# PixiFlood_PTH.net
KiCad netlist of a schematic drawn in EAGLE
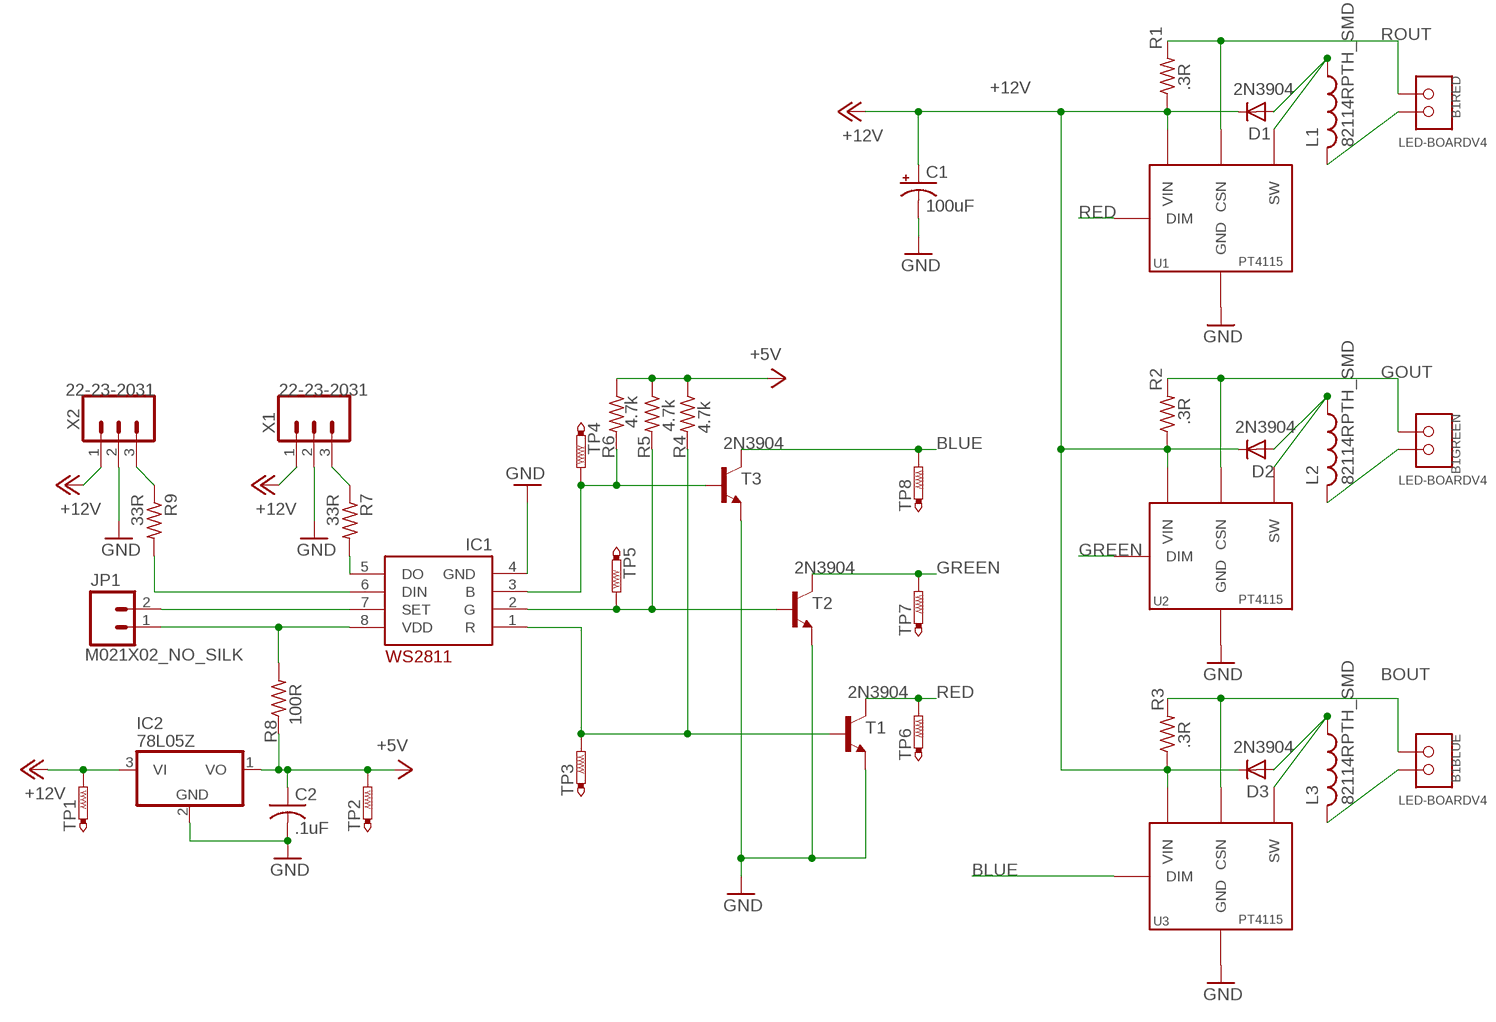
[diagram p0: schematic, sheet 1]

(export (version "E")
  (design (tool "Eeschema 10.0.6"))
  (components
    (comp (ref "B1")
      (value "LED-BOARDV4")
      (footprint "eagle-import:LED_BOARD-V4")
      (libsource (lib "eagle-import") (part "LED-BOARDV4"))
    )
    (comp (ref "C1")
      (value "100uF")
      (footprint "eagle-import:TT2D6L")
      (libsource (lib "eagle-import") (part "CPOL-USTT2D6L"))
    )
    (comp (ref "C2")
      (value ".1uF")
      (footprint "eagle-import:C050-024X044")
      (libsource (lib "eagle-import") (part "C-US050-024X044"))
    )
    (comp (ref "D1")
      (value "2N3904")
      (footprint "eagle-import:DO07")
      (libsource (lib "eagle-import") (part "DIODE-DO07"))
    )
    (comp (ref "D2")
      (value "2N3904")
      (footprint "eagle-import:DO07")
      (libsource (lib "eagle-import") (part "DIODE-DO07"))
    )
    (comp (ref "D3")
      (value "2N3904")
      (footprint "eagle-import:DO07")
      (libsource (lib "eagle-import") (part "DIODE-DO07"))
    )
    (comp (ref "IC1")
      (value "WS2811-SOP8")
      (footprint "eagle-import:SO08-SKINNYPADS")
      (libsource (lib "eagle-import") (part "WS2811-SOP8"))
    )
    (comp (ref "IC2")
      (value "78L05Z")
      (footprint "eagle-import:TO92")
      (libsource (lib "eagle-import") (part "78ZL05"))
    )
    (comp (ref "JP1")
      (value "M021X02_NO_SILK")
      (footprint "eagle-import:1X02_NO_SILK")
      (libsource (lib "eagle-import") (part "M021X02_NO_SILK"))
    )
    (comp (ref "L1")
      (value "82114RPTH_SMD")
      (footprint "eagle-import:INDUCTOR")
      (libsource (lib "eagle-import") (part "82114RPTH_SMD"))
    )
    (comp (ref "L2")
      (value "82114RPTH_SMD")
      (footprint "eagle-import:INDUCTOR")
      (libsource (lib "eagle-import") (part "82114RPTH_SMD"))
    )
    (comp (ref "L3")
      (value "82114RPTH_SMD")
      (footprint "eagle-import:INDUCTOR")
      (libsource (lib "eagle-import") (part "82114RPTH_SMD"))
    )
    (comp (ref "R1")
      (value ".3R")
      (footprint "eagle-import:0204_7")
      (libsource (lib "eagle-import") (part "resistor_R-US_0204/7"))
    )
    (comp (ref "R2")
      (value ".3R")
      (footprint "eagle-import:0204_7")
      (libsource (lib "eagle-import") (part "resistor_R-US_0204/7"))
    )
    (comp (ref "R3")
      (value ".3R")
      (footprint "eagle-import:0204_7")
      (libsource (lib "eagle-import") (part "resistor_R-US_0204/7"))
    )
    (comp (ref "R4")
      (value "4.7k")
      (footprint "eagle-import:0204_7")
      (libsource (lib "eagle-import") (part "resistor_R-US_0204/7"))
    )
    (comp (ref "R5")
      (value "4.7k")
      (footprint "eagle-import:0204_7")
      (libsource (lib "eagle-import") (part "resistor_R-US_0204/7"))
    )
    (comp (ref "R6")
      (value "4.7k")
      (footprint "eagle-import:0204_7")
      (libsource (lib "eagle-import") (part "resistor_R-US_0204/7"))
    )
    (comp (ref "R7")
      (value "33R")
      (footprint "eagle-import:0204_7")
      (libsource (lib "eagle-import") (part "R-US_0204/7"))
    )
    (comp (ref "R8")
      (value "100R")
      (footprint "eagle-import:0204_7")
      (libsource (lib "eagle-import") (part "R-US_0204/7"))
    )
    (comp (ref "R9")
      (value "33R")
      (footprint "eagle-import:0204_7")
      (libsource (lib "eagle-import") (part "R-US_0204/7"))
    )
    (comp (ref "T1")
      (value "2N3904")
      (footprint "eagle-import:TO92")
      (libsource (lib "eagle-import") (part "2N3904"))
    )
    (comp (ref "T2")
      (value "2N3904")
      (footprint "eagle-import:TO92")
      (libsource (lib "eagle-import") (part "2N3904"))
    )
    (comp (ref "T3")
      (value "2N3904")
      (footprint "eagle-import:TO92")
      (libsource (lib "eagle-import") (part "2N3904"))
    )
    (comp (ref "TP1")
      (value "PTR1B2,54")
      (footprint "eagle-import:B2,54")
      (libsource (lib "eagle-import") (part "PTR1B2,54"))
    )
    (comp (ref "TP2")
      (value "PTR1B2,54")
      (footprint "eagle-import:B2,54")
      (libsource (lib "eagle-import") (part "PTR1B2,54"))
    )
    (comp (ref "TP3")
      (value "PTR1B1,27")
      (footprint "eagle-import:B1,27")
      (libsource (lib "eagle-import") (part "PTR1B1,27"))
    )
    (comp (ref "TP4")
      (value "PTR1B1,27")
      (footprint "eagle-import:B1,27")
      (libsource (lib "eagle-import") (part "PTR1B1,27"))
    )
    (comp (ref "TP5")
      (value "PTR1B1,27")
      (footprint "eagle-import:B1,27")
      (libsource (lib "eagle-import") (part "PTR1B1,27"))
    )
    (comp (ref "TP6")
      (value "PTR1B1,27")
      (footprint "eagle-import:B1,27")
      (libsource (lib "eagle-import") (part "PTR1B1,27"))
    )
    (comp (ref "TP7")
      (value "PTR1B1,27")
      (footprint "eagle-import:B1,27")
      (libsource (lib "eagle-import") (part "PTR1B1,27"))
    )
    (comp (ref "TP8")
      (value "PTR1B1,27")
      (footprint "eagle-import:B1,27")
      (libsource (lib "eagle-import") (part "PTR1B1,27"))
    )
    (comp (ref "U1")
      (value "PT4115B89E")
      (footprint "eagle-import:SOT89-5")
      (libsource (lib "eagle-import") (part "PT4115B89E"))
    )
    (comp (ref "U2")
      (value "PT4115B89E")
      (footprint "eagle-import:SOT89-5")
      (libsource (lib "eagle-import") (part "PT4115B89E"))
    )
    (comp (ref "U3")
      (value "PT4115B89E")
      (footprint "eagle-import:SOT89-5")
      (libsource (lib "eagle-import") (part "PT4115B89E"))
    )
    (comp (ref "X1")
      (value "22-23-2031")
      (footprint "eagle-import:22-23-2031")
      (fields (field (name "MF") "MOLEX"))
      (libsource (lib "eagle-import") (part "22-23-2031"))
    )
    (comp (ref "X2")
      (value "22-23-2031")
      (footprint "eagle-import:22-23-2031")
      (fields (field (name "MF") "MOLEX"))
      (libsource (lib "eagle-import") (part "22-23-2031"))
    )
  )
  (nets
    (net (code "1") (name "+5V") (class "Default")
      (node (ref "C2") (pin "1") (pinfunction "1_1") (pintype "passive"))
      (node (ref "IC2") (pin "1") (pinfunction "VO_1") (pintype "passive"))
      (node (ref "R4") (pin "1") (pinfunction "1_1") (pintype "passive"))
      (node (ref "R5") (pin "1") (pinfunction "1_1") (pintype "passive"))
      (node (ref "R6") (pin "1") (pinfunction "1_1") (pintype "passive"))
      (node (ref "R8") (pin "1") (pinfunction "1_1") (pintype "passive"))
      (node (ref "TP2") (pin "TP") (pinfunction "TP_TP") (pintype "input"))
    )
    (net (code "2") (name "+12V") (class "Default")
      (node (ref "C1") (pin "+") (pinfunction "+_+") (pintype "passive"))
      (node (ref "D1") (pin "C") (pinfunction "C_C") (pintype "passive"))
      (node (ref "D2") (pin "C") (pinfunction "C_C") (pintype "passive"))
      (node (ref "D3") (pin "C") (pinfunction "C_C") (pintype "passive"))
      (node (ref "IC2") (pin "3") (pinfunction "VI_3") (pintype "input"))
      (node (ref "R1") (pin "1") (pinfunction "1_1") (pintype "passive"))
      (node (ref "R2") (pin "1") (pinfunction "1_1") (pintype "passive"))
      (node (ref "R3") (pin "1") (pinfunction "1_1") (pintype "passive"))
      (node (ref "TP1") (pin "TP") (pinfunction "TP_TP") (pintype "input"))
      (node (ref "U1") (pin "5") (pinfunction "VIN_5") (pintype "power_in"))
      (node (ref "U2") (pin "5") (pinfunction "VIN_5") (pintype "power_in"))
      (node (ref "U3") (pin "5") (pinfunction "VIN_5") (pintype "power_in"))
      (node (ref "X1") (pin "1") (pinfunction "1_1") (pintype "passive"))
      (node (ref "X2") (pin "1") (pinfunction "1_1") (pintype "passive"))
    )
    (net (code "3") (name "/BLUE") (class "Default")
      (node (ref "T3") (pin "1") (pinfunction "C_1") (pintype "passive"))
      (node (ref "TP8") (pin "TP") (pinfunction "TP_TP") (pintype "input"))
      (node (ref "U3") (pin "3") (pinfunction "DIM_3") (pintype "bidirectional"))
    )
    (net (code "4") (name "/BOUT") (class "Default")
      (node (ref "B1") (pin "B+") (pinfunction "P$2_B+") (pintype "bidirectional"))
      (node (ref "B1") (pin "B+@2") (pinfunction "P$2_B+@2") (pintype "bidirectional"))
      (node (ref "R3") (pin "2") (pinfunction "2_2") (pintype "passive"))
      (node (ref "U3") (pin "4") (pinfunction "CSN_4") (pintype "bidirectional"))
    )
    (net (code "5") (name "/GOUT") (class "Default")
      (node (ref "B1") (pin "G+") (pinfunction "P$2_G+") (pintype "bidirectional"))
      (node (ref "B1") (pin "G+@1") (pinfunction "P$2_G+@1") (pintype "bidirectional"))
      (node (ref "R2") (pin "2") (pinfunction "2_2") (pintype "passive"))
      (node (ref "U2") (pin "4") (pinfunction "CSN_4") (pintype "bidirectional"))
    )
    (net (code "6") (name "/GREEN") (class "Default")
      (node (ref "T2") (pin "1") (pinfunction "C_1") (pintype "passive"))
      (node (ref "TP7") (pin "TP") (pinfunction "TP_TP") (pintype "input"))
      (node (ref "U2") (pin "3") (pinfunction "DIM_3") (pintype "bidirectional"))
    )
    (net (code "7") (name "/RED") (class "Default")
      (node (ref "T1") (pin "1") (pinfunction "C_1") (pintype "passive"))
      (node (ref "TP6") (pin "TP") (pinfunction "TP_TP") (pintype "input"))
      (node (ref "U1") (pin "3") (pinfunction "DIM_3") (pintype "bidirectional"))
    )
    (net (code "8") (name "/ROUT") (class "Default")
      (node (ref "B1") (pin "R+") (pinfunction "P$2_R+") (pintype "bidirectional"))
      (node (ref "B1") (pin "R+@1") (pinfunction "P$2_R+@1") (pintype "bidirectional"))
      (node (ref "R1") (pin "2") (pinfunction "2_2") (pintype "passive"))
      (node (ref "U1") (pin "4") (pinfunction "CSN_4") (pintype "bidirectional"))
    )
    (net (code "9") (name "GND") (class "Default")
      (node (ref "C1") (pin "-") (pinfunction "-_-") (pintype "passive"))
      (node (ref "C2") (pin "2") (pinfunction "2_2") (pintype "passive"))
      (node (ref "IC1") (pin "4") (pinfunction "GND_4") (pintype "power_in"))
      (node (ref "IC2") (pin "2") (pinfunction "GND_2") (pintype "passive"))
      (node (ref "T1") (pin "3") (pinfunction "E_3") (pintype "passive"))
      (node (ref "T2") (pin "3") (pinfunction "E_3") (pintype "passive"))
      (node (ref "T3") (pin "3") (pinfunction "E_3") (pintype "passive"))
      (node (ref "U1") (pin "2") (pinfunction "GND_2") (pintype "power_in"))
      (node (ref "U1") (pin "2@1") (pinfunction "GND_2@1") (pintype "power_in"))
      (node (ref "U1") (pin "2@2") (pinfunction "GND_2@2") (pintype "power_in"))
      (node (ref "U1") (pin "2@3") (pinfunction "GND_2@3") (pintype "power_in"))
      (node (ref "U2") (pin "2") (pinfunction "GND_2") (pintype "power_in"))
      (node (ref "U2") (pin "2@1") (pinfunction "GND_2@1") (pintype "power_in"))
      (node (ref "U2") (pin "2@2") (pinfunction "GND_2@2") (pintype "power_in"))
      (node (ref "U2") (pin "2@3") (pinfunction "GND_2@3") (pintype "power_in"))
      (node (ref "U3") (pin "2") (pinfunction "GND_2") (pintype "power_in"))
      (node (ref "U3") (pin "2@1") (pinfunction "GND_2@1") (pintype "power_in"))
      (node (ref "U3") (pin "2@2") (pinfunction "GND_2@2") (pintype "power_in"))
      (node (ref "U3") (pin "2@3") (pinfunction "GND_2@3") (pintype "power_in"))
      (node (ref "X1") (pin "2") (pinfunction "2_2") (pintype "passive"))
      (node (ref "X2") (pin "2") (pinfunction "2_2") (pintype "passive"))
    )
    (net (code "10") (name "Net-(B1A-P$1-PadB-)") (class "Default")
      (node (ref "B1") (pin "B-") (pinfunction "P$1_B-") (pintype "bidirectional"))
      (node (ref "B1") (pin "B-@1") (pinfunction "P$1_B-@1") (pintype "bidirectional"))
      (node (ref "L3") (pin "2") (pinfunction "2_2") (pintype "passive"))
      (node (ref "L3") (pin "2@A") (pinfunction "2_2@A") (pintype "passive"))
    )
    (net (code "11") (name "Net-(B1B-P$1-PadG-)") (class "Default")
      (node (ref "B1") (pin "G-") (pinfunction "P$1_G-") (pintype "bidirectional"))
      (node (ref "B1") (pin "G-@1") (pinfunction "P$1_G-@1") (pintype "bidirectional"))
      (node (ref "L2") (pin "2") (pinfunction "2_2") (pintype "passive"))
      (node (ref "L2") (pin "2@A") (pinfunction "2_2@A") (pintype "passive"))
    )
    (net (code "12") (name "Net-(B1C-P$1-PadR-)") (class "Default")
      (node (ref "B1") (pin "R-") (pinfunction "P$1_R-") (pintype "bidirectional"))
      (node (ref "B1") (pin "R-@1") (pinfunction "P$1_R-@1") (pintype "bidirectional"))
      (node (ref "L1") (pin "2") (pinfunction "2_2") (pintype "passive"))
      (node (ref "L1") (pin "2@A") (pinfunction "2_2@A") (pintype "passive"))
    )
    (net (code "13") (name "Net-(IC1-B)") (class "Default")
      (node (ref "IC1") (pin "3") (pinfunction "B_3") (pintype "open_collector"))
      (node (ref "R6") (pin "2") (pinfunction "2_2") (pintype "passive"))
      (node (ref "T3") (pin "2") (pinfunction "B_2") (pintype "passive"))
      (node (ref "TP4") (pin "TP") (pinfunction "TP_TP") (pintype "input"))
    )
    (net (code "14") (name "Net-(IC1-DIN)") (class "Default")
      (node (ref "IC1") (pin "6") (pinfunction "DIN_6") (pintype "input"))
      (node (ref "R9") (pin "2") (pinfunction "2_2") (pintype "passive"))
    )
    (net (code "15") (name "Net-(IC1-DO)") (class "Default")
      (node (ref "IC1") (pin "5") (pinfunction "DO_5") (pintype "output"))
      (node (ref "R7") (pin "2") (pinfunction "2_2") (pintype "passive"))
    )
    (net (code "16") (name "Net-(IC1-G)") (class "Default")
      (node (ref "IC1") (pin "2") (pinfunction "G_2") (pintype "open_collector"))
      (node (ref "R5") (pin "2") (pinfunction "2_2") (pintype "passive"))
      (node (ref "T2") (pin "2") (pinfunction "B_2") (pintype "passive"))
      (node (ref "TP5") (pin "TP") (pinfunction "TP_TP") (pintype "input"))
    )
    (net (code "17") (name "Net-(IC1-R)") (class "Default")
      (node (ref "IC1") (pin "1") (pinfunction "R_1") (pintype "open_collector"))
      (node (ref "R4") (pin "2") (pinfunction "2_2") (pintype "passive"))
      (node (ref "T1") (pin "2") (pinfunction "B_2") (pintype "passive"))
      (node (ref "TP3") (pin "TP") (pinfunction "TP_TP") (pintype "input"))
    )
    (net (code "18") (name "Net-(IC1-SET)") (class "Default")
      (node (ref "IC1") (pin "7") (pinfunction "SET_7") (pintype "input"))
      (node (ref "JP1") (pin "2") (pinfunction "2_2") (pintype "passive"))
    )
    (net (code "19") (name "Net-(IC1-VDD)") (class "Default")
      (node (ref "IC1") (pin "8") (pinfunction "VDD_8") (pintype "power_in"))
      (node (ref "JP1") (pin "1") (pinfunction "1_1") (pintype "passive"))
      (node (ref "R8") (pin "2") (pinfunction "2_2") (pintype "passive"))
    )
    (net (code "20") (name "Net-(R7-Pad1)") (class "Default")
      (node (ref "R7") (pin "1") (pinfunction "1_1") (pintype "passive"))
      (node (ref "X1") (pin "3") (pinfunction "3_3") (pintype "passive"))
    )
    (net (code "21") (name "Net-(R9-Pad1)") (class "Default")
      (node (ref "R9") (pin "1") (pinfunction "1_1") (pintype "passive"))
      (node (ref "X2") (pin "3") (pinfunction "3_3") (pintype "passive"))
    )
    (net (code "22") (name "Net-(U1-SW)") (class "Default")
      (node (ref "D1") (pin "A") (pinfunction "A_A") (pintype "passive"))
      (node (ref "L1") (pin "1") (pinfunction "1_1") (pintype "passive"))
      (node (ref "L1") (pin "1@A") (pinfunction "1_1@A") (pintype "passive"))
      (node (ref "U1") (pin "1") (pinfunction "SW_1") (pintype "bidirectional"))
    )
    (net (code "23") (name "Net-(U2-SW)") (class "Default")
      (node (ref "D2") (pin "A") (pinfunction "A_A") (pintype "passive"))
      (node (ref "L2") (pin "1") (pinfunction "1_1") (pintype "passive"))
      (node (ref "L2") (pin "1@A") (pinfunction "1_1@A") (pintype "passive"))
      (node (ref "U2") (pin "1") (pinfunction "SW_1") (pintype "bidirectional"))
    )
    (net (code "24") (name "Net-(U3-SW)") (class "Default")
      (node (ref "D3") (pin "A") (pinfunction "A_A") (pintype "passive"))
      (node (ref "L3") (pin "1") (pinfunction "1_1") (pintype "passive"))
      (node (ref "L3") (pin "1@A") (pinfunction "1_1@A") (pintype "passive"))
      (node (ref "U3") (pin "1") (pinfunction "SW_1") (pintype "bidirectional"))
    )
  )
)
